# CANBridge.net
KiCad netlist of a schematic drawn in EAGLE
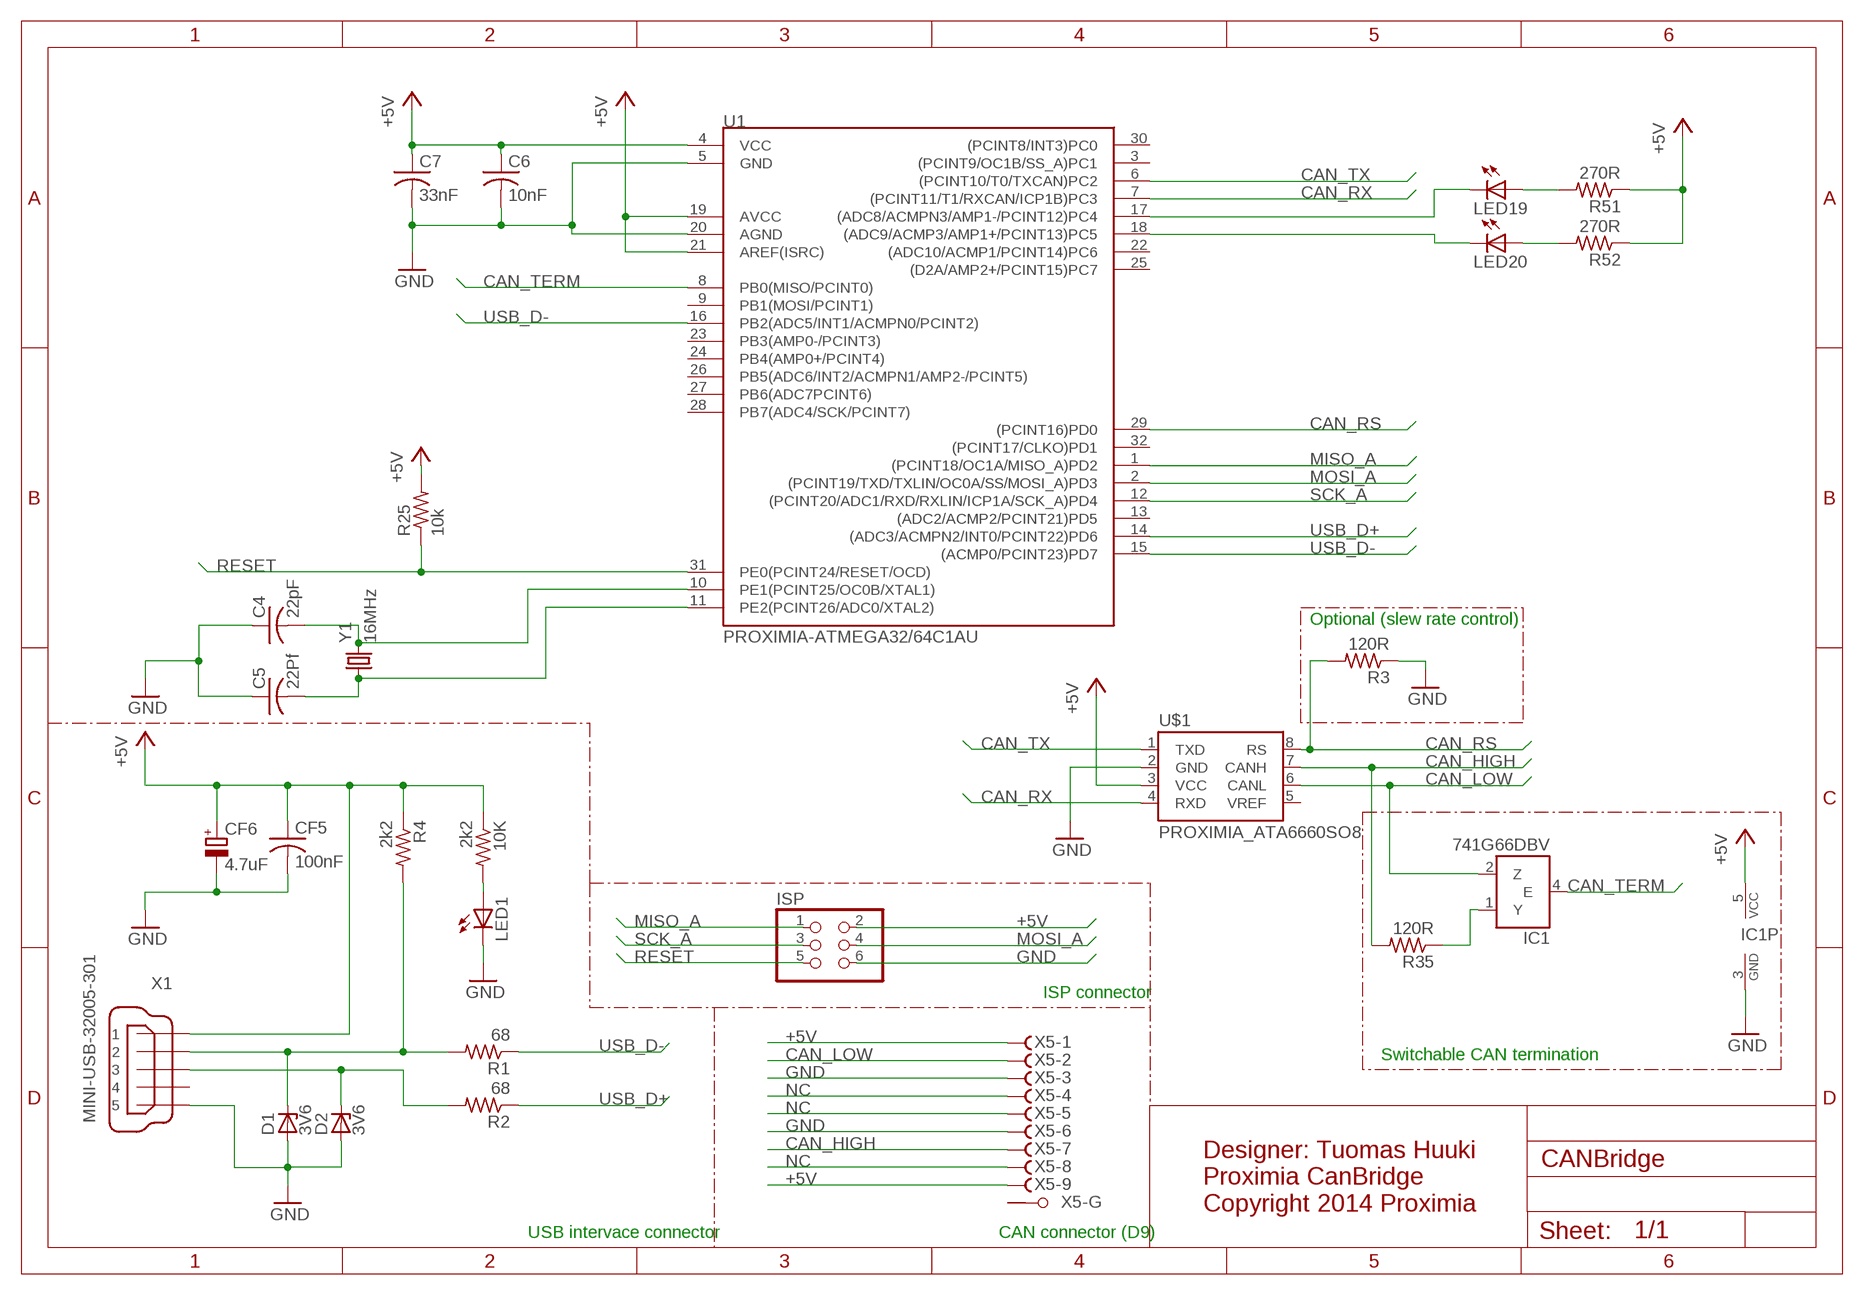
[diagram p0: schematic, sheet 1]

(export (version "E")
  (design (tool "Eeschema 10.0.6"))
  (components
    (comp (ref "10K")
      (value "2k2")
      (footprint "eagle-import:R0603")
      (libsource (lib "eagle-import") (part "R-US_R0603"))
    )
    (comp (ref "C4")
      (value "22pF")
      (footprint "eagle-import:C0603")
      (libsource (lib "eagle-import") (part "C-USC0603"))
    )
    (comp (ref "C5")
      (value "22Pf")
      (footprint "eagle-import:C0603")
      (libsource (lib "eagle-import") (part "C-USC0603"))
    )
    (comp (ref "C6")
      (value "10nF")
      (footprint "eagle-import:C0603")
      (libsource (lib "eagle-import") (part "resistor_C-USC0603"))
    )
    (comp (ref "C7")
      (value "33nF")
      (footprint "eagle-import:C0603")
      (libsource (lib "eagle-import") (part "resistor_C-USC0603"))
    )
    (comp (ref "CF5")
      (value "100nF")
      (footprint "eagle-import:C0603")
      (libsource (lib "eagle-import") (part "C-USC0603"))
    )
    (comp (ref "CF6")
      (value "4.7uF")
      (footprint "eagle-import:PANASONIC_B")
      (libsource (lib "eagle-import") (part "CPOL-EUB"))
    )
    (comp (ref "D1")
      (value "3V6")
      (footprint "eagle-import:SOD80C")
      (libsource (lib "eagle-import") (part "ZENER-DIODESOD80C"))
    )
    (comp (ref "D2")
      (value "3V6")
      (footprint "eagle-import:SOD80C")
      (libsource (lib "eagle-import") (part "ZENER-DIODESOD80C"))
    )
    (comp (ref "IC1")
      (value "741G66DBV")
      (footprint "eagle-import:SOT23-5")
      (libsource (lib "eagle-import") (part "741G66DBV"))
    )
    (comp (ref "ISP")
      (value "PINHD-2X3")
      (footprint "eagle-import:2X03")
      (libsource (lib "eagle-import") (part "PINHD-2X3"))
    )
    (comp (ref "LED1")
      (value "LEDSML1206")
      (footprint "eagle-import:SML1206")
      (libsource (lib "eagle-import") (part "LEDSML1206"))
    )
    (comp (ref "LED19")
      (value "LEDSML1206")
      (footprint "eagle-import:SML1206")
      (libsource (lib "eagle-import") (part "LEDSML1206"))
    )
    (comp (ref "LED20")
      (value "LEDSML1206")
      (footprint "eagle-import:SML1206")
      (libsource (lib "eagle-import") (part "LEDSML1206"))
    )
    (comp (ref "R1")
      (value "68")
      (footprint "eagle-import:R0603")
      (libsource (lib "eagle-import") (part "R-US_R0603"))
    )
    (comp (ref "R2")
      (value "68")
      (footprint "eagle-import:R0603")
      (libsource (lib "eagle-import") (part "R-US_R0603"))
    )
    (comp (ref "R3")
      (value "120R")
      (footprint "eagle-import:R0603")
      (libsource (lib "eagle-import") (part "resistor_R-US_R0603"))
    )
    (comp (ref "R4")
      (value "2k2")
      (footprint "eagle-import:R0603")
      (libsource (lib "eagle-import") (part "R-US_R0603"))
    )
    (comp (ref "R25")
      (value "10k")
      (footprint "eagle-import:R0603")
      (libsource (lib "eagle-import") (part "resistor_R-US_R0603"))
    )
    (comp (ref "R35")
      (value "120R")
      (footprint "eagle-import:R0603")
      (libsource (lib "eagle-import") (part "resistor_R-US_R0603"))
    )
    (comp (ref "R51")
      (value "270R")
      (footprint "eagle-import:R0603")
      (libsource (lib "eagle-import") (part "R-US_R0603"))
    )
    (comp (ref "R52")
      (value "270R")
      (footprint "eagle-import:R0603")
      (libsource (lib "eagle-import") (part "R-US_R0603"))
    )
    (comp (ref "U$1")
      (value "PROXIMIA_ATA6660SO8")
      (footprint "eagle-import:PROXIMIA_SO08")
      (libsource (lib "eagle-import") (part "PROXIMIA_ATA6660SO8"))
    )
    (comp (ref "U1")
      (value "PROXIMIA-ATMEGA32/64C1AU")
      (footprint "eagle-import:PROXIMIA_TQFP32-08")
      (libsource (lib "eagle-import") (part "PROXIMIA-ATMEGA32/64C1AU"))
    )
    (comp (ref "X1")
      (value "MINI-USB-32005-301")
      (footprint "eagle-import:32005-301")
      (libsource (lib "eagle-import") (part "MINI-USB-32005-301"))
    )
    (comp (ref "X5")
      (value "F09HPS")
      (footprint "eagle-import:F09HP")
      (libsource (lib "eagle-import") (part "F09HPS"))
    )
    (comp (ref "Y1")
      (value "16MHz")
      (footprint "eagle-import:CRYSTAL-SMD-5X3")
      (libsource (lib "eagle-import") (part "CRYSTAL5X3"))
    )
  )
  (nets
    (net (code "1") (name "+5V") (class "Default")
      (node (ref "10K") (pin "1") (pinfunction "1_1") (pintype "passive"))
      (node (ref "C6") (pin "1") (pinfunction "1_1") (pintype "passive"))
      (node (ref "C7") (pin "1") (pinfunction "1_1") (pintype "passive"))
      (node (ref "CF5") (pin "1") (pinfunction "1_1") (pintype "passive"))
      (node (ref "CF6") (pin "+") (pinfunction "+_+") (pintype "passive"))
      (node (ref "IC1") (pin "5") (pinfunction "VCC_5") (pintype "power_in"))
      (node (ref "ISP") (pin "2") (pinfunction "2_2") (pintype "passive"))
      (node (ref "R25") (pin "2") (pinfunction "2_2") (pintype "passive"))
      (node (ref "R4") (pin "1") (pinfunction "1_1") (pintype "passive"))
      (node (ref "R51") (pin "1") (pinfunction "1_1") (pintype "passive"))
      (node (ref "R52") (pin "1") (pinfunction "1_1") (pintype "passive"))
      (node (ref "U$1") (pin "3") (pinfunction "VCC_3") (pintype "bidirectional"))
      (node (ref "U1") (pin "19") (pinfunction "AVCC_19") (pintype "bidirectional"))
      (node (ref "U1") (pin "21") (pinfunction "AREF(ISRC)_21") (pintype "bidirectional"))
      (node (ref "U1") (pin "4") (pinfunction "VCC_4") (pintype "bidirectional"))
      (node (ref "X1") (pin "1") (pinfunction "1_1") (pintype "passive"))
      (node (ref "X5") (pin "1") (pinfunction "F_1") (pintype "passive"))
      (node (ref "X5") (pin "9") (pinfunction "F_9") (pintype "passive"))
    )
    (net (code "2") (name "/CAN_HIGH") (class "Default")
      (node (ref "R35") (pin "2") (pinfunction "2_2") (pintype "passive"))
      (node (ref "U$1") (pin "7") (pinfunction "CANH_7") (pintype "bidirectional"))
      (node (ref "X5") (pin "7") (pinfunction "F_7") (pintype "passive"))
    )
    (net (code "3") (name "/CAN_LOW") (class "Default")
      (node (ref "IC1") (pin "2") (pinfunction "Z_2") (pintype "bidirectional"))
      (node (ref "U$1") (pin "6") (pinfunction "CANL_6") (pintype "bidirectional"))
      (node (ref "X5") (pin "2") (pinfunction "F_2") (pintype "passive"))
    )
    (net (code "4") (name "/CAN_RS") (class "Default")
      (node (ref "R3") (pin "2") (pinfunction "2_2") (pintype "passive"))
      (node (ref "U$1") (pin "8") (pinfunction "RS_8") (pintype "bidirectional"))
      (node (ref "U1") (pin "29") (pinfunction "(PCINT16)PD0_29") (pintype "bidirectional"))
    )
    (net (code "5") (name "/CAN_RX") (class "Default")
      (node (ref "U$1") (pin "4") (pinfunction "RXD_4") (pintype "bidirectional"))
      (node (ref "U1") (pin "7") (pinfunction "(PCINT11/T1/RXCAN/ICP1B)PC3_7") (pintype "bidirectional"))
    )
    (net (code "6") (name "/CAN_TERM") (class "Default")
      (node (ref "IC1") (pin "4") (pinfunction "E_4") (pintype "input"))
      (node (ref "U1") (pin "8") (pinfunction "PB0(MISO/PCINT0)_8") (pintype "bidirectional"))
    )
    (net (code "7") (name "/CAN_TX") (class "Default")
      (node (ref "U$1") (pin "1") (pinfunction "TXD_1") (pintype "bidirectional"))
      (node (ref "U1") (pin "6") (pinfunction "(PCINT10/T0/TXCAN)PC2_6") (pintype "bidirectional"))
    )
    (net (code "8") (name "/MISO_A") (class "Default")
      (node (ref "ISP") (pin "1") (pinfunction "1_1") (pintype "passive"))
      (node (ref "U1") (pin "1") (pinfunction "(PCINT18/OC1A/MISO_A)PD2_1") (pintype "bidirectional"))
    )
    (net (code "9") (name "/MOSI_A") (class "Default")
      (node (ref "ISP") (pin "4") (pinfunction "4_4") (pintype "passive"))
      (node (ref "U1") (pin "2") (pinfunction "(PCINT19/TXD/TXLIN/OC0A/SS/MOSI_A)PD3_2") (pintype "bidirectional"))
    )
    (net (code "10") (name "/NC") (class "Default")
      (node (ref "X5") (pin "4") (pinfunction "F_4") (pintype "passive"))
      (node (ref "X5") (pin "5") (pinfunction "F_5") (pintype "passive"))
      (node (ref "X5") (pin "8") (pinfunction "F_8") (pintype "passive"))
    )
    (net (code "11") (name "/RESET") (class "Default")
      (node (ref "ISP") (pin "5") (pinfunction "5_5") (pintype "passive"))
      (node (ref "R25") (pin "1") (pinfunction "1_1") (pintype "passive"))
      (node (ref "U1") (pin "31") (pinfunction "PE0(PCINT24/RESET/OCD)_31") (pintype "bidirectional"))
    )
    (net (code "12") (name "/SCK_A") (class "Default")
      (node (ref "ISP") (pin "3") (pinfunction "3_3") (pintype "passive"))
      (node (ref "U1") (pin "12") (pinfunction "(PCINT20/ADC1/RXD/RXLIN/ICP1A/SCK_A)PD4_12") (pintype "bidirectional"))
    )
    (net (code "13") (name "/USB_D+") (class "Default")
      (node (ref "R2") (pin "1") (pinfunction "1_1") (pintype "passive"))
      (node (ref "U1") (pin "14") (pinfunction "(ADC3/ACMPN2/INT0/PCINT22)PD6_14") (pintype "bidirectional"))
    )
    (net (code "14") (name "/USB_D-") (class "Default")
      (node (ref "R1") (pin "1") (pinfunction "1_1") (pintype "passive"))
      (node (ref "U1") (pin "15") (pinfunction "(ACMP0/PCINT23)PD7_15") (pintype "bidirectional"))
      (node (ref "U1") (pin "16") (pinfunction "PB2(ADC5/INT1/ACMPN0/PCINT2)_16") (pintype "bidirectional"))
    )
    (net (code "15") (name "GND") (class "Default")
      (node (ref "C4") (pin "1") (pinfunction "1_1") (pintype "passive"))
      (node (ref "C5") (pin "1") (pinfunction "1_1") (pintype "passive"))
      (node (ref "C6") (pin "2") (pinfunction "2_2") (pintype "passive"))
      (node (ref "C7") (pin "2") (pinfunction "2_2") (pintype "passive"))
      (node (ref "CF5") (pin "2") (pinfunction "2_2") (pintype "passive"))
      (node (ref "CF6") (pin "-") (pinfunction "-_-") (pintype "passive"))
      (node (ref "D1") (pin "A") (pinfunction "A_A") (pintype "passive"))
      (node (ref "D2") (pin "A") (pinfunction "A_A") (pintype "passive"))
      (node (ref "IC1") (pin "3") (pinfunction "GND_3") (pintype "power_in"))
      (node (ref "ISP") (pin "6") (pinfunction "6_6") (pintype "passive"))
      (node (ref "LED1") (pin "C") (pinfunction "C_C") (pintype "passive"))
      (node (ref "R3") (pin "1") (pinfunction "1_1") (pintype "passive"))
      (node (ref "U$1") (pin "2") (pinfunction "GND_2") (pintype "bidirectional"))
      (node (ref "U1") (pin "20") (pinfunction "AGND_20") (pintype "bidirectional"))
      (node (ref "U1") (pin "5") (pinfunction "GND_5") (pintype "bidirectional"))
      (node (ref "X1") (pin "5") (pinfunction "5_5") (pintype "passive"))
      (node (ref "X5") (pin "3") (pinfunction "F_3") (pintype "passive"))
      (node (ref "X5") (pin "6") (pinfunction "F_6") (pintype "passive"))
    )
    (net (code "16") (name "Net-(10K-Pad2)") (class "Default")
      (node (ref "10K") (pin "2") (pinfunction "2_2") (pintype "passive"))
      (node (ref "LED1") (pin "A") (pinfunction "A_A") (pintype "passive"))
    )
    (net (code "17") (name "Net-(D1-PadC)") (class "Default")
      (node (ref "D1") (pin "C") (pinfunction "C_C") (pintype "passive"))
      (node (ref "R1") (pin "2") (pinfunction "2_2") (pintype "passive"))
      (node (ref "R4") (pin "2") (pinfunction "2_2") (pintype "passive"))
      (node (ref "X1") (pin "2") (pinfunction "2_2") (pintype "passive"))
    )
    (net (code "18") (name "Net-(D2-PadC)") (class "Default")
      (node (ref "D2") (pin "C") (pinfunction "C_C") (pintype "passive"))
      (node (ref "R2") (pin "2") (pinfunction "2_2") (pintype "passive"))
      (node (ref "X1") (pin "3") (pinfunction "3_3") (pintype "passive"))
    )
    (net (code "19") (name "Net-(IC1A-Y)") (class "Default")
      (node (ref "IC1") (pin "1") (pinfunction "Y_1") (pintype "bidirectional"))
      (node (ref "R35") (pin "1") (pinfunction "1_1") (pintype "passive"))
    )
    (net (code "20") (name "Net-(LED19-PadA)") (class "Default")
      (node (ref "LED19") (pin "A") (pinfunction "A_A") (pintype "passive"))
      (node (ref "R51") (pin "2") (pinfunction "2_2") (pintype "passive"))
    )
    (net (code "21") (name "Net-(LED20-PadA)") (class "Default")
      (node (ref "LED20") (pin "A") (pinfunction "A_A") (pintype "passive"))
      (node (ref "R52") (pin "2") (pinfunction "2_2") (pintype "passive"))
    )
    (net (code "22") (name "Net-(U1-(ADC8{slash}ACMPN3{slash}AMP1-{slash}PCINT12)PC4)") (class "Default")
      (node (ref "LED19") (pin "C") (pinfunction "C_C") (pintype "passive"))
      (node (ref "U1") (pin "17") (pinfunction "(ADC8/ACMPN3/AMP1-/PCINT12)PC4_17") (pintype "bidirectional"))
    )
    (net (code "23") (name "Net-(U1-(ADC9{slash}ACMP3{slash}AMP1+{slash}PCINT13)PC5)") (class "Default")
      (node (ref "LED20") (pin "C") (pinfunction "C_C") (pintype "passive"))
      (node (ref "U1") (pin "18") (pinfunction "(ADC9/ACMP3/AMP1+/PCINT13)PC5_18") (pintype "bidirectional"))
    )
    (net (code "24") (name "Net-(U1-PE1(PCINT25{slash}OC0B{slash}XTAL1))") (class "Default")
      (node (ref "C4") (pin "2") (pinfunction "2_2") (pintype "passive"))
      (node (ref "U1") (pin "10") (pinfunction "PE1(PCINT25/OC0B/XTAL1)_10") (pintype "bidirectional"))
      (node (ref "Y1") (pin "3") (pinfunction "2_3") (pintype "passive"))
    )
    (net (code "25") (name "Net-(U1-PE2(PCINT26{slash}ADC0{slash}XTAL2))") (class "Default")
      (node (ref "C5") (pin "2") (pinfunction "2_2") (pintype "passive"))
      (node (ref "U1") (pin "11") (pinfunction "PE2(PCINT26/ADC0/XTAL2)_11") (pintype "bidirectional"))
      (node (ref "Y1") (pin "1") (pinfunction "1_1") (pintype "passive"))
    )
    (net (code "26") (name "unconnected-(U$1-VREF-Pad5)") (class "Default")
      (node (ref "U$1") (pin "5") (pinfunction "VREF_5") (pintype "bidirectional"))
    )
    (net (code "27") (name "unconnected-(U1-(ADC2{slash}ACMP2{slash}PCINT21)PD5-Pad13)") (class "Default")
      (node (ref "U1") (pin "13") (pinfunction "(ADC2/ACMP2/PCINT21)PD5_13") (pintype "bidirectional"))
    )
    (net (code "28") (name "unconnected-(U1-(ADC10{slash}ACMP1{slash}PCINT14)PC6-Pad22)") (class "Default")
      (node (ref "U1") (pin "22") (pinfunction "(ADC10/ACMP1/PCINT14)PC6_22") (pintype "bidirectional"))
    )
    (net (code "29") (name "unconnected-(U1-(D2A{slash}AMP2+{slash}PCINT15)PC7-Pad25)") (class "Default")
      (node (ref "U1") (pin "25") (pinfunction "(D2A/AMP2+/PCINT15)PC7_25") (pintype "bidirectional"))
    )
    (net (code "30") (name "unconnected-(U1-(PCINT8{slash}INT3)PC0-Pad30)") (class "Default")
      (node (ref "U1") (pin "30") (pinfunction "(PCINT8/INT3)PC0_30") (pintype "bidirectional"))
    )
    (net (code "31") (name "unconnected-(U1-(PCINT9{slash}OC1B{slash}SS_A)PC1-Pad3)") (class "Default")
      (node (ref "U1") (pin "3") (pinfunction "(PCINT9/OC1B/SS_A)PC1_3") (pintype "bidirectional"))
    )
    (net (code "32") (name "unconnected-(U1-(PCINT17{slash}CLKO)PD1-Pad32)") (class "Default")
      (node (ref "U1") (pin "32") (pinfunction "(PCINT17/CLKO)PD1_32") (pintype "bidirectional"))
    )
    (net (code "33") (name "unconnected-(U1-PB1(MOSI{slash}PCINT1)-Pad9)") (class "Default")
      (node (ref "U1") (pin "9") (pinfunction "PB1(MOSI/PCINT1)_9") (pintype "bidirectional"))
    )
    (net (code "34") (name "unconnected-(U1-PB3(AMP0-{slash}PCINT3)-Pad23)") (class "Default")
      (node (ref "U1") (pin "23") (pinfunction "PB3(AMP0-/PCINT3)_23") (pintype "bidirectional"))
    )
    (net (code "35") (name "unconnected-(U1-PB4(AMP0+{slash}PCINT4)-Pad24)") (class "Default")
      (node (ref "U1") (pin "24") (pinfunction "PB4(AMP0+/PCINT4)_24") (pintype "bidirectional"))
    )
    (net (code "36") (name "unconnected-(U1-PB5(ADC6{slash}INT2{slash}ACMPN1{slash}AMP2-{slash}PCINT5)-Pad26)") (class "Default")
      (node (ref "U1") (pin "26") (pinfunction "PB5(ADC6/INT2/ACMPN1/AMP2-/PCINT5)_26") (pintype "bidirectional"))
    )
    (net (code "37") (name "unconnected-(U1-PB6(ADC7PCINT6)-Pad27)") (class "Default")
      (node (ref "U1") (pin "27") (pinfunction "PB6(ADC7PCINT6)_27") (pintype "bidirectional"))
    )
    (net (code "38") (name "unconnected-(U1-PB7(ADC4{slash}SCK{slash}PCINT7)-Pad28)") (class "Default")
      (node (ref "U1") (pin "28") (pinfunction "PB7(ADC4/SCK/PCINT7)_28") (pintype "bidirectional"))
    )
    (net (code "39") (name "unconnected-(X1-Pad4)") (class "Default")
      (node (ref "X1") (pin "4") (pinfunction "4_4") (pintype "passive"))
    )
    (net (code "40") (name "unconnected-(X5-PadG1)") (class "Default")
      (node (ref "X5") (pin "G1") (pinfunction "G1_G1") (pintype "passive"))
    )
    (net (code "41") (name "unconnected-(X5-PadG2)") (class "Default")
      (node (ref "X5") (pin "G2") (pinfunction "G2_G2") (pintype "passive"))
    )
  )
)
